# 2__FPGA.net
KiCad netlist of a schematic drawn in Altium Designer
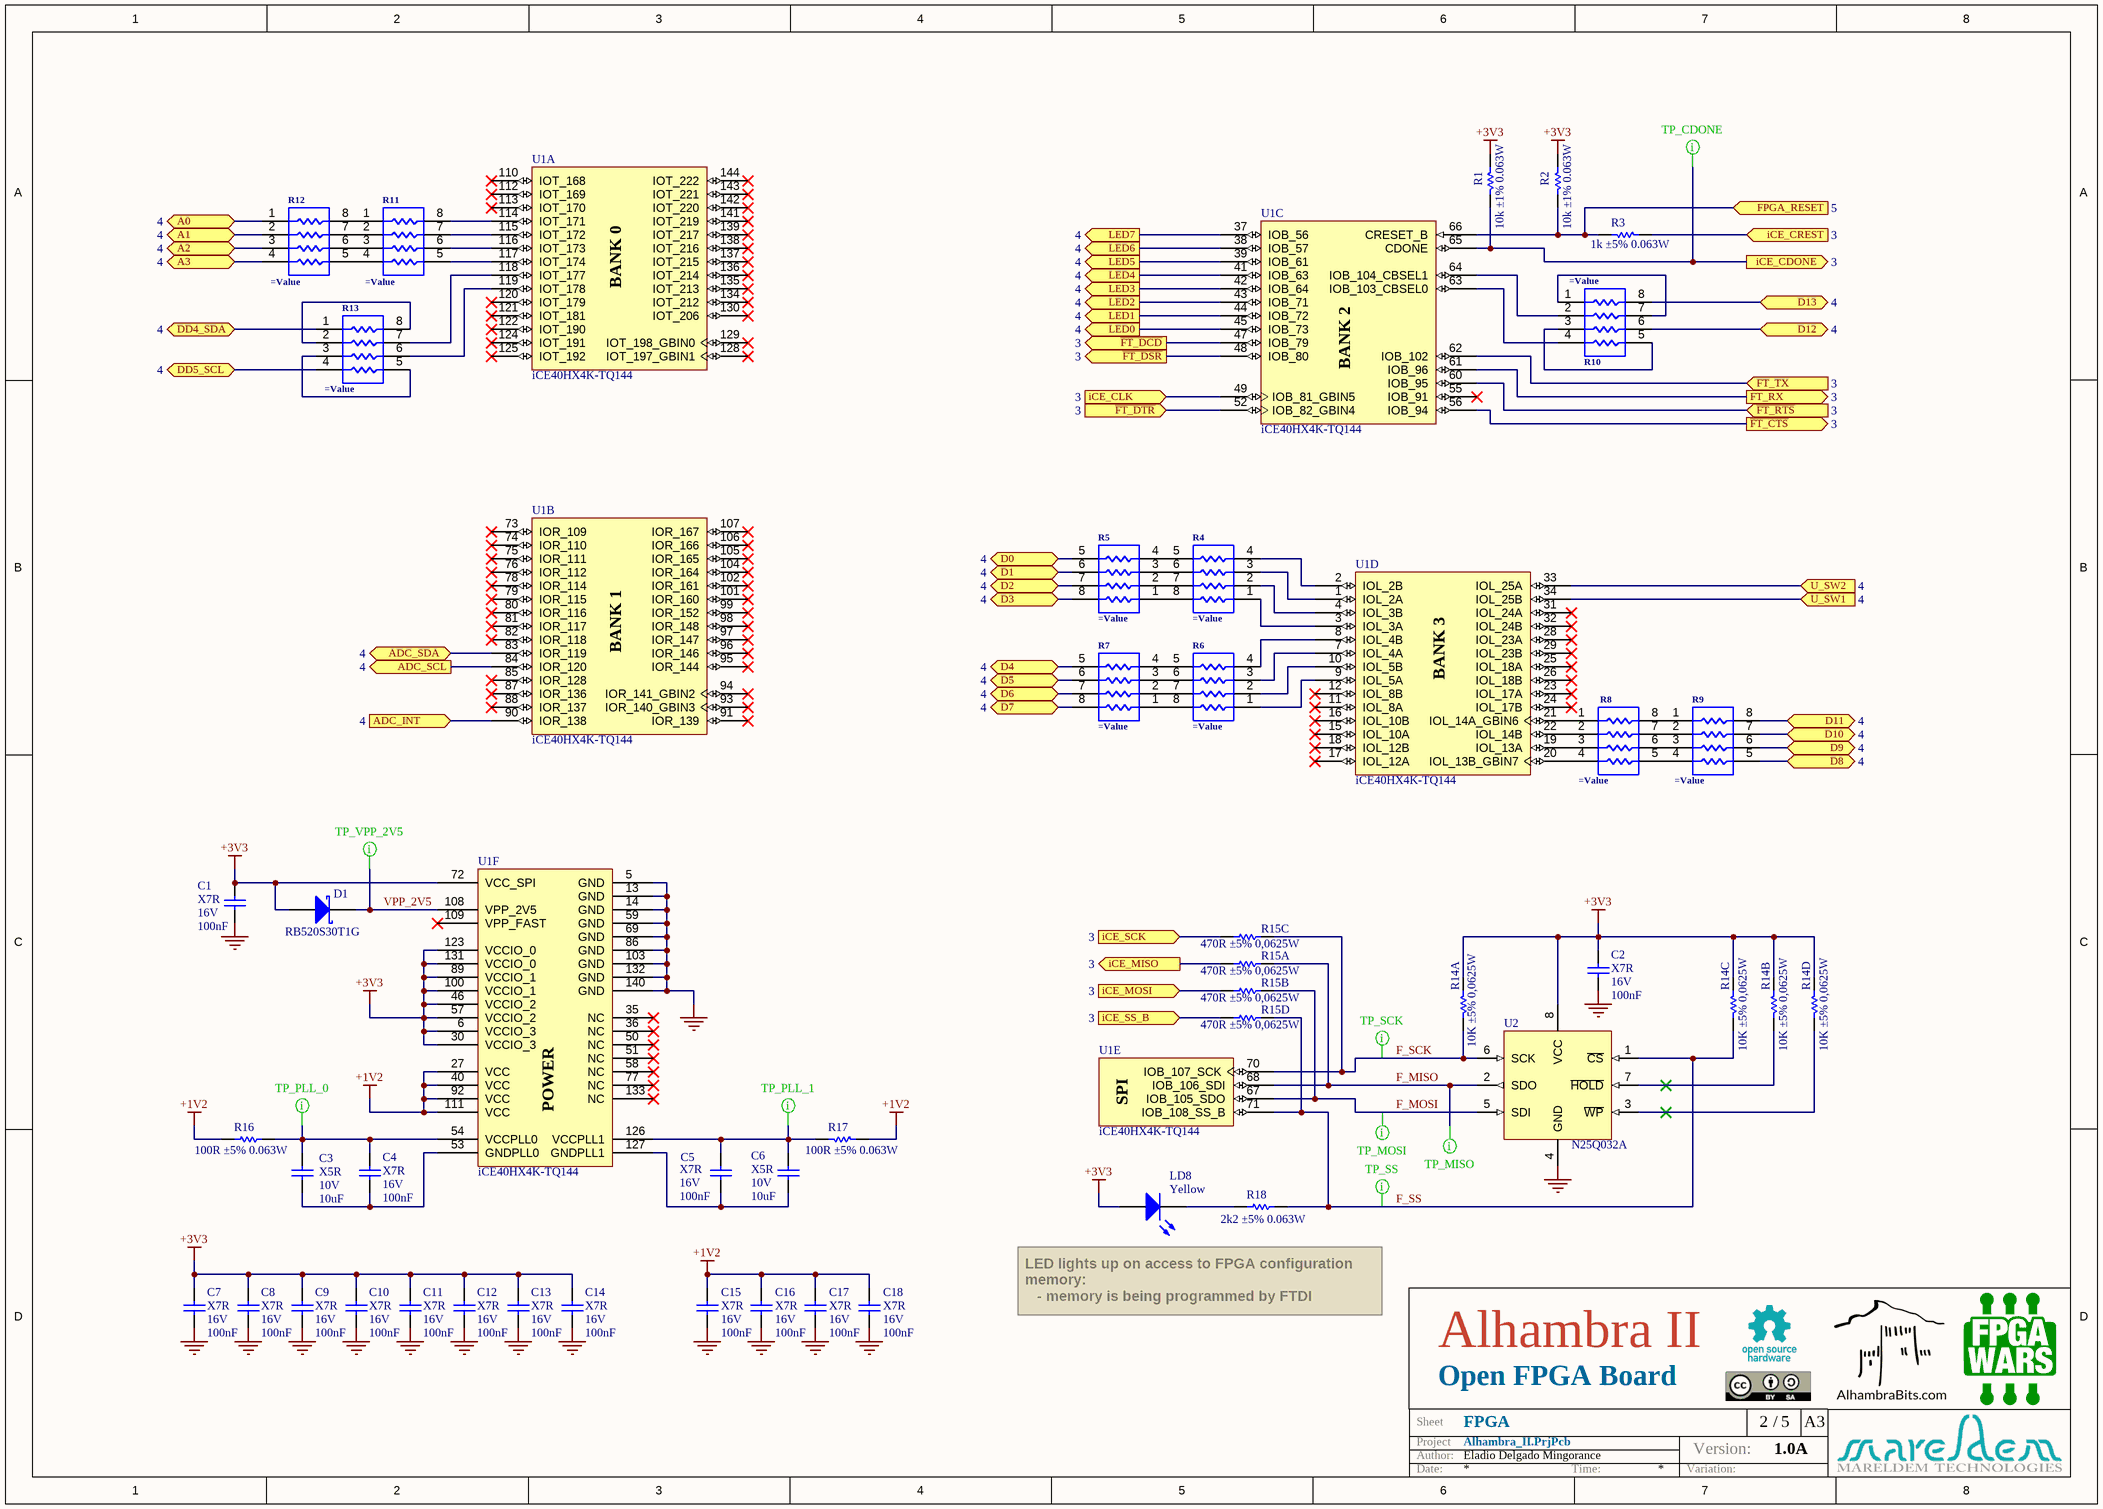
[diagram p0: [2]_FPGA.SchDoc]

(export (version "E")
  (design (tool "Eeschema 10.0.6"))
  (components
    (comp (ref "C1")
      (value "Capacitor")
      (footprint "C0402")
      (description "Capacitor SMD")
      (fields
        (field (name "DIELECTRIC") "X7R")
        (field (name "VOLTAGE") "16V")
        (field (name "CAPACITANCE") "100nF")
        (field (name "PART NUMBER") "C0402_100nF_16V_±10%")
        (field (name "TOLERANCE") "±10%")
      )
      (libsource (lib "Pasives_Capacitor_SMD") (part "Capacitor"))
    )
    (comp (ref "C2")
      (value "Capacitor")
      (footprint "C0402")
      (description "Capacitor SMD")
      (fields
        (field (name "DIELECTRIC") "X7R")
        (field (name "VOLTAGE") "16V")
        (field (name "CAPACITANCE") "100nF")
        (field (name "PART NUMBER") "C0402_100nF_16V_±10%")
        (field (name "TOLERANCE") "±10%")
      )
      (libsource (lib "Pasives_Capacitor_SMD") (part "Capacitor"))
    )
    (comp (ref "C3")
      (value "Capacitor")
      (footprint "C0603")
      (description "Capacitor SMD")
      (fields
        (field (name "DIELECTRIC") "X5R")
        (field (name "VOLTAGE") "10V")
        (field (name "CAPACITANCE") "10uF")
        (field (name "PART NUMBER") "C0603_10uF_10V_±10%")
        (field (name "TOLERANCE") "±10%")
      )
      (libsource (lib "") (part "Capacitor_1"))
    )
    (comp (ref "C4")
      (value "Capacitor")
      (footprint "C0402")
      (description "Capacitor SMD")
      (fields
        (field (name "DIELECTRIC") "X7R")
        (field (name "VOLTAGE") "16V")
        (field (name "CAPACITANCE") "100nF")
        (field (name "PART NUMBER") "C0402_100nF_16V_±10%")
        (field (name "TOLERANCE") "±10%")
      )
      (libsource (lib "Pasives_Capacitor_SMD") (part "Capacitor"))
    )
    (comp (ref "C5")
      (value "Capacitor")
      (footprint "C0402")
      (description "Capacitor SMD")
      (fields
        (field (name "DIELECTRIC") "X7R")
        (field (name "VOLTAGE") "16V")
        (field (name "CAPACITANCE") "100nF")
        (field (name "PART NUMBER") "C0402_100nF_16V_±10%")
        (field (name "TOLERANCE") "±10%")
      )
      (libsource (lib "Pasives_Capacitor_SMD") (part "Capacitor"))
    )
    (comp (ref "C6")
      (value "Capacitor")
      (footprint "C0603")
      (description "Capacitor SMD")
      (fields
        (field (name "DIELECTRIC") "X5R")
        (field (name "VOLTAGE") "10V")
        (field (name "CAPACITANCE") "10uF")
        (field (name "PART NUMBER") "C0603_10uF_10V_±10%")
        (field (name "TOLERANCE") "±10%")
      )
      (libsource (lib "") (part "Capacitor_1"))
    )
    (comp (ref "C7")
      (value "Capacitor")
      (footprint "C0402:C0402")
      (description "Capacitor SMD")
      (fields
        (field (name "DIELECTRIC") "X7R")
        (field (name "VOLTAGE") "16V")
        (field (name "CAPACITANCE") "100nF")
        (field (name "PART NUMBER") "C0402_100nF_16V_±10%")
        (field (name "TOLERANCE") "±10%")
      )
      (libsource (lib "Pasives_Capacitor_SMD") (part "Capacitor"))
    )
    (comp (ref "C8")
      (value "Capacitor")
      (footprint "C0402:C0402")
      (description "Capacitor SMD")
      (fields
        (field (name "DIELECTRIC") "X7R")
        (field (name "VOLTAGE") "16V")
        (field (name "CAPACITANCE") "100nF")
        (field (name "PART NUMBER") "C0402_100nF_16V_±10%")
        (field (name "TOLERANCE") "±10%")
      )
      (libsource (lib "Pasives_Capacitor_SMD") (part "Capacitor"))
    )
    (comp (ref "C9")
      (value "Capacitor")
      (footprint "C0402")
      (description "Capacitor SMD")
      (fields
        (field (name "DIELECTRIC") "X7R")
        (field (name "VOLTAGE") "16V")
        (field (name "CAPACITANCE") "100nF")
        (field (name "PART NUMBER") "C0402_100nF_16V_±10%")
        (field (name "TOLERANCE") "±10%")
      )
      (libsource (lib "Pasives_Capacitor_SMD") (part "Capacitor"))
    )
    (comp (ref "C10")
      (value "Capacitor")
      (footprint "C0402")
      (description "Capacitor SMD")
      (fields
        (field (name "DIELECTRIC") "X7R")
        (field (name "VOLTAGE") "16V")
        (field (name "CAPACITANCE") "100nF")
        (field (name "PART NUMBER") "C0402_100nF_16V_±10%")
        (field (name "TOLERANCE") "±10%")
      )
      (libsource (lib "Pasives_Capacitor_SMD") (part "Capacitor"))
    )
    (comp (ref "C11")
      (value "Capacitor")
      (footprint "C0402")
      (description "Capacitor SMD")
      (fields
        (field (name "DIELECTRIC") "X7R")
        (field (name "VOLTAGE") "16V")
        (field (name "CAPACITANCE") "100nF")
        (field (name "PART NUMBER") "C0402_100nF_16V_±10%")
        (field (name "TOLERANCE") "±10%")
      )
      (libsource (lib "Pasives_Capacitor_SMD") (part "Capacitor"))
    )
    (comp (ref "C12")
      (value "Capacitor")
      (footprint "C0402")
      (description "Capacitor SMD")
      (fields
        (field (name "DIELECTRIC") "X7R")
        (field (name "VOLTAGE") "16V")
        (field (name "CAPACITANCE") "100nF")
        (field (name "PART NUMBER") "C0402_100nF_16V_±10%")
        (field (name "TOLERANCE") "±10%")
      )
      (libsource (lib "Pasives_Capacitor_SMD") (part "Capacitor"))
    )
    (comp (ref "C13")
      (value "Capacitor")
      (footprint "C0402")
      (description "Capacitor SMD")
      (fields
        (field (name "DIELECTRIC") "X7R")
        (field (name "VOLTAGE") "16V")
        (field (name "CAPACITANCE") "100nF")
        (field (name "PART NUMBER") "C0402_100nF_16V_±10%")
        (field (name "TOLERANCE") "±10%")
      )
      (libsource (lib "Pasives_Capacitor_SMD") (part "Capacitor"))
    )
    (comp (ref "C14")
      (value "Capacitor")
      (footprint "C0402")
      (description "Capacitor SMD")
      (fields
        (field (name "DIELECTRIC") "X7R")
        (field (name "VOLTAGE") "16V")
        (field (name "CAPACITANCE") "100nF")
        (field (name "PART NUMBER") "C0402_100nF_16V_±10%")
        (field (name "TOLERANCE") "±10%")
      )
      (libsource (lib "Pasives_Capacitor_SMD") (part "Capacitor"))
    )
    (comp (ref "C15")
      (value "Capacitor")
      (footprint "C0402")
      (description "Capacitor SMD")
      (fields
        (field (name "DIELECTRIC") "X7R")
        (field (name "VOLTAGE") "16V")
        (field (name "CAPACITANCE") "100nF")
        (field (name "PART NUMBER") "C0402_100nF_16V_±10%")
        (field (name "TOLERANCE") "±10%")
      )
      (libsource (lib "Pasives_Capacitor_SMD") (part "Capacitor"))
    )
    (comp (ref "C16")
      (value "Capacitor")
      (footprint "C0402")
      (description "Capacitor SMD")
      (fields
        (field (name "DIELECTRIC") "X7R")
        (field (name "VOLTAGE") "16V")
        (field (name "CAPACITANCE") "100nF")
        (field (name "PART NUMBER") "C0402_100nF_16V_±10%")
        (field (name "TOLERANCE") "±10%")
      )
      (libsource (lib "Pasives_Capacitor_SMD") (part "Capacitor"))
    )
    (comp (ref "C17")
      (value "Capacitor")
      (footprint "C0402")
      (description "Capacitor SMD")
      (fields
        (field (name "DIELECTRIC") "X7R")
        (field (name "VOLTAGE") "16V")
        (field (name "CAPACITANCE") "100nF")
        (field (name "PART NUMBER") "C0402_100nF_16V_±10%")
        (field (name "TOLERANCE") "±10%")
      )
      (libsource (lib "Pasives_Capacitor_SMD") (part "Capacitor"))
    )
    (comp (ref "C18")
      (value "Capacitor")
      (footprint "C0402")
      (description "Capacitor SMD")
      (fields
        (field (name "DIELECTRIC") "X7R")
        (field (name "VOLTAGE") "16V")
        (field (name "CAPACITANCE") "100nF")
        (field (name "PART NUMBER") "C0402_100nF_16V_±10%")
        (field (name "TOLERANCE") "±10%")
      )
      (libsource (lib "Pasives_Capacitor_SMD") (part "Capacitor"))
    )
    (comp (ref "D1")
      (value "RB520S30T1G")
      (footprint "SOD523")
      (description "Schottky Diode")
      (fields (field (name "MANUFACTURER") "On Semiconductor"))
      (libsource (lib "Diodes") (part "Schottky"))
    )
    (comp (ref "LD8")
      (value "Yellow")
      (footprint "LED0603")
      (description "LED")
      (fields (field (name "PART NUMBER") "LED Yellow 0603 Wurth") (field (name "MANUFACTURER") "WE"))
      (libsource (lib "Optoelectronics") (part "LED"))
    )
    (comp (ref "R1")
      (value "10k ±1% 0.063W")
      (footprint "R0402")
      (description "Resistor, SMD")
      (fields (field (name "TOLERANCE") "±1%") (field (name "POWER") "0.063W"))
      (libsource (lib "Pasives_Resistor_SMD") (part "Resistor"))
    )
    (comp (ref "R2")
      (value "10k ±1% 0.063W")
      (footprint "R0402")
      (description "Resistor, SMD")
      (fields (field (name "TOLERANCE") "±1%") (field (name "POWER") "0.063W"))
      (libsource (lib "Pasives_Resistor_SMD") (part "Resistor"))
    )
    (comp (ref "R3")
      (value "1k ±5% 0.063W")
      (footprint "R0402")
      (description "Resistor, SMD")
      (fields (field (name "TOLERANCE") "±5%") (field (name "POWER") "0.063W"))
      (libsource (lib "Pasives_Resistor_SMD") (part "Resistor"))
    )
    (comp (ref "R4")
      (value "~")
      (footprint "4xArray_1206_Convex")
      (description "Resistor, Array 4x1")
      (fields
        (field (name "PART NUMBER") "4xArray_1206_Convex_100R_0,0625W_0,05")
        (field (name "POWER") "0,0625W")
      )
      (libsource (lib "Pasives_Resistor_SMD") (part "Resistor_4x"))
    )
    (comp (ref "R5")
      (value "~")
      (footprint "4xArray_1206_Convex")
      (description "Resistor, Array 4x1")
      (fields
        (field (name "PART NUMBER") "4xArray_1206_Convex_100R_0,0625W_0,05")
        (field (name "POWER") "0,0625W")
      )
      (libsource (lib "Pasives_Resistor_SMD") (part "Resistor_4x"))
    )
    (comp (ref "R6")
      (value "~")
      (footprint "4xArray_1206_Convex")
      (description "Resistor, Array 4x1")
      (fields
        (field (name "PART NUMBER") "4xArray_1206_Convex_100R_0,0625W_0,05")
        (field (name "POWER") "0,0625W")
      )
      (libsource (lib "Pasives_Resistor_SMD") (part "Resistor_4x"))
    )
    (comp (ref "R7")
      (value "~")
      (footprint "4xArray_1206_Convex")
      (description "Resistor, Array 4x1")
      (fields
        (field (name "PART NUMBER") "4xArray_1206_Convex_100R_0,0625W_0,05")
        (field (name "POWER") "0,0625W")
      )
      (libsource (lib "Pasives_Resistor_SMD") (part "Resistor_4x"))
    )
    (comp (ref "R8")
      (value "~")
      (footprint "4xArray_1206_Convex")
      (description "Resistor, Array 4x1")
      (fields
        (field (name "PART NUMBER") "4xArray_1206_Convex_100R_0,0625W_0,05")
        (field (name "POWER") "0,0625W")
      )
      (libsource (lib "Pasives_Resistor_SMD") (part "Resistor_4x"))
    )
    (comp (ref "R9")
      (value "~")
      (footprint "4xArray_1206_Convex")
      (description "Resistor, Array 4x1")
      (fields
        (field (name "PART NUMBER") "4xArray_1206_Convex_100R_0,0625W_0,05")
        (field (name "POWER") "0,0625W")
      )
      (libsource (lib "Pasives_Resistor_SMD") (part "Resistor_4x"))
    )
    (comp (ref "R10")
      (value "~")
      (footprint "4xArray_1206_Convex")
      (description "Resistor, Array 4x1")
      (fields
        (field (name "PART NUMBER") "4xArray_1206_Convex_100R_0,0625W_0,05")
        (field (name "POWER") "0,0625W")
      )
      (libsource (lib "Pasives_Resistor_SMD") (part "Resistor_4x"))
    )
    (comp (ref "R11")
      (value "~")
      (footprint "4xArray_1206_Convex")
      (description "Resistor, Array 4x1")
      (fields
        (field (name "PART NUMBER") "4xArray_1206_Convex_100R_0,0625W_0,05")
        (field (name "POWER") "0,0625W")
      )
      (libsource (lib "Pasives_Resistor_SMD") (part "Resistor_4x"))
    )
    (comp (ref "R12")
      (value "~")
      (footprint "4xArray_1206_Convex")
      (description "Resistor, Array 4x1")
      (fields
        (field (name "PART NUMBER") "4xArray_1206_Convex_100R_0,0625W_0,05")
        (field (name "POWER") "0,0625W")
      )
      (libsource (lib "Pasives_Resistor_SMD") (part "Resistor_4x"))
    )
    (comp (ref "R13")
      (value "~")
      (footprint "4xArray_1206_Convex")
      (description "Resistor, Array 4x1")
      (fields
        (field (name "PART NUMBER") "4xArray_1206_Convex_100R_0,0625W_0,05")
        (field (name "POWER") "0,0625W")
      )
      (libsource (lib "Pasives_Resistor_SMD") (part "Resistor_4x"))
    )
    (comp (ref "R14")
      (value "10K ±5% 0,0625W")
      (footprint "4xArray_1206_Convex")
      (description "Resistor")
      (fields (field (name "TOLERANCE") "±5%") (field (name "POWER") "0,0625W"))
      (libsource (lib "Pasives_Resistor_SMD") (part "Resistor_x4_Parts"))
    )
    (comp (ref "R15")
      (value "470R ±5% 0,0625W")
      (footprint "4xArray_1206_Convex")
      (description "Resistor")
      (fields (field (name "TOLERANCE") "±5%") (field (name "POWER") "0,0625W"))
      (libsource (lib "Pasives_Resistor_SMD") (part "Resistor_x4_Parts"))
    )
    (comp (ref "R16")
      (value "100R ±5% 0.063W")
      (footprint "R0402")
      (description "Resistor, SMD")
      (fields (field (name "TOLERANCE") "±5%") (field (name "POWER") "0.063W"))
      (libsource (lib "Pasives_Resistor_SMD") (part "Resistor"))
    )
    (comp (ref "R17")
      (value "100R ±5% 0.063W")
      (footprint "R0402")
      (description "Resistor, SMD")
      (fields (field (name "TOLERANCE") "±5%") (field (name "POWER") "0.063W"))
      (libsource (lib "Pasives_Resistor_SMD") (part "Resistor"))
    )
    (comp (ref "R18")
      (value "2k2 ±5% 0.063W")
      (footprint "R0402")
      (description "Resistor, SMD")
      (fields (field (name "TOLERANCE") "±5%") (field (name "POWER") "0.063W"))
      (libsource (lib "Pasives_Resistor_SMD") (part "Resistor"))
    )
    (comp (ref "U1")
      (value "iCE40HX4K-TQ144")
      (footprint "TQFP-144_HX4K_FPGAwars")
      (fields (field (name "PART NUMBER") "iCE40-HX4K") (field (name "MANUFACTURER") "Lattice"))
      (libsource (lib "FPGA") (part "iCE40HX4K-TQ144"))
    )
    (comp (ref "U2")
      (value "N25Q032A")
      (footprint "DFN-8 6x5mm")
      (description "NOR Flash Memory, serial")
      (fields (field (name "MANUFACTURER") "Micron"))
      (libsource (lib "Memory_Serial") (part "N25Q032A"))
    )
  )
  (nets
    (net (code "1") (name "+1V2") (class "Default")
      (node (ref "C15") (pin "2") (pinfunction "2_2") (pintype "passive"))
      (node (ref "C16") (pin "2") (pinfunction "2_2") (pintype "passive"))
      (node (ref "C17") (pin "2") (pinfunction "2_2") (pintype "passive"))
      (node (ref "C18") (pin "2") (pinfunction "2_2") (pintype "passive"))
      (node (ref "R16") (pin "2") (pinfunction "2_2") (pintype "passive"))
      (node (ref "R17") (pin "2") (pinfunction "2_2") (pintype "passive"))
      (node (ref "U1") (pin "111") (pinfunction "VCC_111") (pintype "power_in"))
      (node (ref "U1") (pin "27") (pinfunction "VCC_27") (pintype "power_in"))
      (node (ref "U1") (pin "40") (pinfunction "VCC_40") (pintype "power_in"))
      (node (ref "U1") (pin "92") (pinfunction "VCC_92") (pintype "power_in"))
    )
    (net (code "2") (name "+3V3") (class "Default")
      (node (ref "C1") (pin "2") (pinfunction "2_2") (pintype "passive"))
      (node (ref "C10") (pin "2") (pinfunction "2_2") (pintype "passive"))
      (node (ref "C11") (pin "2") (pinfunction "2_2") (pintype "passive"))
      (node (ref "C12") (pin "2") (pinfunction "2_2") (pintype "passive"))
      (node (ref "C13") (pin "2") (pinfunction "2_2") (pintype "passive"))
      (node (ref "C14") (pin "2") (pinfunction "2_2") (pintype "passive"))
      (node (ref "C2") (pin "1") (pinfunction "1_1") (pintype "passive"))
      (node (ref "C7") (pin "2") (pinfunction "2_2") (pintype "passive"))
      (node (ref "C8") (pin "2") (pinfunction "2_2") (pintype "passive"))
      (node (ref "C9") (pin "2") (pinfunction "2_2") (pintype "passive"))
      (node (ref "D1") (pin "A") (pinfunction "A_A") (pintype "passive"))
      (node (ref "LD8") (pin "A") (pinfunction "A_A") (pintype "passive"))
      (node (ref "R1") (pin "1") (pinfunction "1_1") (pintype "passive"))
      (node (ref "R14") (pin "1") (pinfunction "1_1") (pintype "passive"))
      (node (ref "R14") (pin "2") (pinfunction "2_2") (pintype "passive"))
      (node (ref "R14") (pin "3") (pinfunction "3_3") (pintype "passive"))
      (node (ref "R14") (pin "4") (pinfunction "4_4") (pintype "passive"))
      (node (ref "R2") (pin "1") (pinfunction "1_1") (pintype "passive"))
      (node (ref "U1") (pin "100") (pinfunction "VCCIO_1_100") (pintype "power_in"))
      (node (ref "U1") (pin "123") (pinfunction "VCCIO_0_123") (pintype "power_in"))
      (node (ref "U1") (pin "131") (pinfunction "VCCIO_0_131") (pintype "power_in"))
      (node (ref "U1") (pin "30") (pinfunction "VCCIO_3_30") (pintype "power_in"))
      (node (ref "U1") (pin "46") (pinfunction "VCCIO_2_46") (pintype "power_in"))
      (node (ref "U1") (pin "57") (pinfunction "VCCIO_2_57") (pintype "power_in"))
      (node (ref "U1") (pin "6") (pinfunction "VCCIO_3_6") (pintype "power_in"))
      (node (ref "U1") (pin "72") (pinfunction "VCC_SPI_72") (pintype "power_in"))
      (node (ref "U1") (pin "89") (pinfunction "VCCIO_1_89") (pintype "power_in"))
      (node (ref "U2") (pin "8") (pinfunction "VCC_8") (pintype "power_in"))
    )
    (net (code "3") (name "/A0") (class "Default")
      (node (ref "R12") (pin "1") (pinfunction "1_1") (pintype "passive"))
    )
    (net (code "4") (name "/A1") (class "Default")
      (node (ref "R12") (pin "2") (pinfunction "2_2") (pintype "passive"))
    )
    (net (code "5") (name "/A2") (class "Default")
      (node (ref "R12") (pin "3") (pinfunction "3_3") (pintype "passive"))
    )
    (net (code "6") (name "/A3") (class "Default")
      (node (ref "R12") (pin "4") (pinfunction "4_4") (pintype "passive"))
    )
    (net (code "7") (name "/ADC_INT") (class "Default")
      (node (ref "U1") (pin "90") (pinfunction "IOR_138_90") (pintype "bidirectional"))
    )
    (net (code "8") (name "/ADC_SCL") (class "Default")
      (node (ref "U1") (pin "84") (pinfunction "IOR_120_84") (pintype "bidirectional"))
    )
    (net (code "9") (name "/ADC_SDA") (class "Default")
      (node (ref "U1") (pin "83") (pinfunction "IOR_119_83") (pintype "bidirectional"))
    )
    (net (code "10") (name "/D0") (class "Default")
      (node (ref "R5") (pin "5") (pinfunction "5_5") (pintype "passive"))
    )
    (net (code "11") (name "/D1") (class "Default")
      (node (ref "R5") (pin "6") (pinfunction "6_6") (pintype "passive"))
    )
    (net (code "12") (name "/D2") (class "Default")
      (node (ref "R5") (pin "7") (pinfunction "7_7") (pintype "passive"))
    )
    (net (code "13") (name "/D3") (class "Default")
      (node (ref "R5") (pin "8") (pinfunction "8_8") (pintype "passive"))
    )
    (net (code "14") (name "/D4") (class "Default")
      (node (ref "R7") (pin "5") (pinfunction "5_5") (pintype "passive"))
    )
    (net (code "15") (name "/D5") (class "Default")
      (node (ref "R7") (pin "6") (pinfunction "6_6") (pintype "passive"))
    )
    (net (code "16") (name "/D6") (class "Default")
      (node (ref "R7") (pin "7") (pinfunction "7_7") (pintype "passive"))
    )
    (net (code "17") (name "/D7") (class "Default")
      (node (ref "R7") (pin "8") (pinfunction "8_8") (pintype "passive"))
    )
    (net (code "18") (name "/D8") (class "Default")
      (node (ref "R9") (pin "5") (pinfunction "5_5") (pintype "passive"))
    )
    (net (code "19") (name "/D9") (class "Default")
      (node (ref "R9") (pin "6") (pinfunction "6_6") (pintype "passive"))
    )
    (net (code "20") (name "/D10") (class "Default")
      (node (ref "R9") (pin "7") (pinfunction "7_7") (pintype "passive"))
    )
    (net (code "21") (name "/D11") (class "Default")
      (node (ref "R9") (pin "8") (pinfunction "8_8") (pintype "passive"))
    )
    (net (code "22") (name "/D12") (class "Default")
      (node (ref "R10") (pin "6") (pinfunction "6_6") (pintype "passive"))
    )
    (net (code "23") (name "/D13") (class "Default")
      (node (ref "R10") (pin "8") (pinfunction "8_8") (pintype "passive"))
    )
    (net (code "24") (name "/DD4_SDA") (class "Default")
      (node (ref "R13") (pin "1") (pinfunction "1_1") (pintype "passive"))
    )
    (net (code "25") (name "/DD5_SCL") (class "Default")
      (node (ref "R13") (pin "4") (pinfunction "4_4") (pintype "passive"))
    )
    (net (code "26") (name "/FPGA_RESET") (class "Default")
      (node (ref "R2") (pin "2") (pinfunction "2_2") (pintype "passive"))
      (node (ref "R3") (pin "2") (pinfunction "2_2") (pintype "passive"))
      (node (ref "U1") (pin "66") (pinfunction "CRESET_B_66") (pintype "input"))
    )
    (net (code "27") (name "/FT_CTS") (class "Default")
      (node (ref "U1") (pin "56") (pinfunction "IOB_94_56") (pintype "bidirectional"))
    )
    (net (code "28") (name "/FT_DCD") (class "Default")
      (node (ref "U1") (pin "47") (pinfunction "IOB_79_47") (pintype "bidirectional"))
    )
    (net (code "29") (name "/FT_DSR") (class "Default")
      (node (ref "U1") (pin "48") (pinfunction "IOB_80_48") (pintype "bidirectional"))
    )
    (net (code "30") (name "/FT_DTR") (class "Default")
      (node (ref "U1") (pin "52") (pinfunction "IOB_82_GBIN4_52") (pintype "bidirectional"))
    )
    (net (code "31") (name "/FT_RTS") (class "Default")
      (node (ref "U1") (pin "60") (pinfunction "IOB_95_60") (pintype "bidirectional"))
    )
    (net (code "32") (name "/FT_RX") (class "Default")
      (node (ref "U1") (pin "61") (pinfunction "IOB_96_61") (pintype "bidirectional"))
    )
    (net (code "33") (name "/FT_TX") (class "Default")
      (node (ref "U1") (pin "62") (pinfunction "IOB_102_62") (pintype "bidirectional"))
    )
    (net (code "34") (name "/F_MISO") (class "Default")
      (node (ref "R15") (pin "8") (pinfunction "8_8") (pintype "passive"))
      (node (ref "U1") (pin "68") (pinfunction "IOB_45_SDI_68") (pintype "bidirectional"))
      (node (ref "U2") (pin "2") (pinfunction "SDO_2") (pintype "output"))
    )
    (net (code "35") (name "/F_MOSI") (class "Default")
      (node (ref "R15") (pin "7") (pinfunction "7_7") (pintype "passive"))
      (node (ref "U1") (pin "67") (pinfunction "IOB_44_SDO_67") (pintype "bidirectional"))
      (node (ref "U2") (pin "5") (pinfunction "SDI_5") (pintype "input"))
    )
    (net (code "36") (name "/F_SCK") (class "Default")
      (node (ref "R14") (pin "8") (pinfunction "8_8") (pintype "passive"))
      (node (ref "R15") (pin "6") (pinfunction "6_6") (pintype "passive"))
      (node (ref "U1") (pin "70") (pinfunction "IOB_46_SCK_70") (pintype "bidirectional"))
      (node (ref "U2") (pin "6") (pinfunction "SCK_6") (pintype "input"))
    )
    (net (code "37") (name "/F_SS") (class "Default")
      (node (ref "R14") (pin "6") (pinfunction "6_6") (pintype "passive"))
      (node (ref "R15") (pin "5") (pinfunction "5_5") (pintype "passive"))
      (node (ref "R18") (pin "2") (pinfunction "2_2") (pintype "passive"))
      (node (ref "U1") (pin "71") (pinfunction "IOB_47_SS_B_71") (pintype "bidirectional"))
      (node (ref "U2") (pin "1") (pinfunction "CS_1") (pintype "input"))
    )
    (net (code "38") (name "/LED0") (class "Default")
      (node (ref "U1") (pin "45") (pinfunction "IOB_73_45") (pintype "bidirectional"))
    )
    (net (code "39") (name "/LED1") (class "Default")
      (node (ref "U1") (pin "44") (pinfunction "IOB_72_44") (pintype "bidirectional"))
    )
    (net (code "40") (name "/LED2") (class "Default")
      (node (ref "U1") (pin "43") (pinfunction "IOB_71_43") (pintype "bidirectional"))
    )
    (net (code "41") (name "/LED3") (class "Default")
      (node (ref "U1") (pin "42") (pinfunction "IOB_64_42") (pintype "bidirectional"))
    )
    (net (code "42") (name "/LED4") (class "Default")
      (node (ref "U1") (pin "41") (pinfunction "IOB_63_41") (pintype "bidirectional"))
    )
    (net (code "43") (name "/LED5") (class "Default")
      (node (ref "U1") (pin "39") (pinfunction "IOB_61_39") (pintype "bidirectional"))
    )
    (net (code "44") (name "/LED6") (class "Default")
      (node (ref "U1") (pin "38") (pinfunction "IOB_57_38") (pintype "bidirectional"))
    )
    (net (code "45") (name "/LED7") (class "Default")
      (node (ref "U1") (pin "37") (pinfunction "IOB_56_37") (pintype "bidirectional"))
    )
    (net (code "46") (name "/U_SW1") (class "Default")
      (node (ref "U1") (pin "34") (pinfunction "IOL_25B_34") (pintype "bidirectional"))
    )
    (net (code "47") (name "/U_SW2") (class "Default")
      (node (ref "U1") (pin "33") (pinfunction "IOL_25A_33") (pintype "bidirectional"))
    )
    (net (code "48") (name "/VPP_2V5") (class "Default")
      (node (ref "D1") (pin "k") (pinfunction "K_k") (pintype "passive"))
      (node (ref "U1") (pin "108") (pinfunction "VPP_2V5_108") (pintype "power_in"))
    )
    (net (code "49") (name "/iCE_CDONE") (class "Default")
      (node (ref "R1") (pin "2") (pinfunction "2_2") (pintype "passive"))
      (node (ref "U1") (pin "65") (pinfunction "CDONE_65") (pintype "bidirectional"))
    )
    (net (code "50") (name "/iCE_CLK") (class "Default")
      (node (ref "U1") (pin "49") (pinfunction "IOB_81_GBIN5_49") (pintype "bidirectional"))
    )
    (net (code "51") (name "/iCE_CREST") (class "Default")
      (node (ref "R3") (pin "1") (pinfunction "1_1") (pintype "passive"))
    )
    (net (code "52") (name "/iCE_MISO") (class "Default")
      (node (ref "R15") (pin "1") (pinfunction "1_1") (pintype "passive"))
    )
    (net (code "53") (name "/iCE_MOSI") (class "Default")
      (node (ref "R15") (pin "2") (pinfunction "2_2") (pintype "passive"))
    )
    (net (code "54") (name "/iCE_SCK") (class "Default")
      (node (ref "R15") (pin "3") (pinfunction "3_3") (pintype "passive"))
    )
    (net (code "55") (name "/iCE_SS_B") (class "Default")
      (node (ref "R15") (pin "4") (pinfunction "4_4") (pintype "passive"))
    )
    (net (code "56") (name "GND") (class "Default")
      (node (ref "C1") (pin "1") (pinfunction "1_1") (pintype "passive"))
      (node (ref "C10") (pin "1") (pinfunction "1_1") (pintype "passive"))
      (node (ref "C11") (pin "1") (pinfunction "1_1") (pintype "passive"))
      (node (ref "C12") (pin "1") (pinfunction "1_1") (pintype "passive"))
      (node (ref "C13") (pin "1") (pinfunction "1_1") (pintype "passive"))
      (node (ref "C14") (pin "1") (pinfunction "1_1") (pintype "passive"))
      (node (ref "C15") (pin "1") (pinfunction "1_1") (pintype "passive"))
      (node (ref "C16") (pin "1") (pinfunction "1_1") (pintype "passive"))
      (node (ref "C17") (pin "1") (pinfunction "1_1") (pintype "passive"))
      (node (ref "C18") (pin "1") (pinfunction "1_1") (pintype "passive"))
      (node (ref "C2") (pin "2") (pinfunction "2_2") (pintype "passive"))
      (node (ref "C7") (pin "1") (pinfunction "1_1") (pintype "passive"))
      (node (ref "C8") (pin "1") (pinfunction "1_1") (pintype "passive"))
      (node (ref "C9") (pin "1") (pinfunction "1_1") (pintype "passive"))
      (node (ref "U1") (pin "103") (pinfunction "GND_103") (pintype "power_in"))
      (node (ref "U1") (pin "13") (pinfunction "GND_13") (pintype "power_in"))
      (node (ref "U1") (pin "132") (pinfunction "GND_132") (pintype "power_in"))
      (node (ref "U1") (pin "14") (pinfunction "GND_14") (pintype "power_in"))
      (node (ref "U1") (pin "140") (pinfunction "GND_140") (pintype "power_in"))
      (node (ref "U1") (pin "5") (pinfunction "GND_5") (pintype "power_in"))
      (node (ref "U1") (pin "59") (pinfunction "GND_59") (pintype "power_in"))
      (node (ref "U1") (pin "69") (pinfunction "GND_69") (pintype "power_in"))
      (node (ref "U1") (pin "86") (pinfunction "GND_86") (pintype "power_in"))
      (node (ref "U2") (pin "4") (pinfunction "GND_4") (pintype "power_in"))
    )
    (net (code "57") (name "Net-(LD8-PadK)") (class "Default")
      (node (ref "LD8") (pin "K") (pinfunction "K_K") (pintype "passive"))
      (node (ref "R18") (pin "1") (pinfunction "1_1") (pintype "passive"))
    )
    (net (code "58") (name "Net-(R4-Pad5)") (class "Default")
      (node (ref "R4") (pin "5") (pinfunction "5_5") (pintype "passive"))
      (node (ref "R5") (pin "4") (pinfunction "4_4") (pintype "passive"))
    )
    (net (code "59") (name "Net-(R4-Pad6)") (class "Default")
      (node (ref "R4") (pin "6") (pinfunction "6_6") (pintype "passive"))
      (node (ref "R5") (pin "3") (pinfunction "3_3") (pintype "passive"))
    )
    (net (code "60") (name "Net-(R4-Pad7)") (class "Default")
      (node (ref "R4") (pin "7") (pinfunction "7_7") (pintype "passive"))
      (node (ref "R5") (pin "2") (pinfunction "2_2") (pintype "passive"))
    )
    (net (code "61") (name "Net-(R4-Pad8)") (class "Default")
      (node (ref "R4") (pin "8") (pinfunction "8_8") (pintype "passive"))
      (node (ref "R5") (pin "1") (pinfunction "1_1") (pintype "passive"))
    )
    (net (code "62") (name "Net-(R6-Pad5)") (class "Default")
      (node (ref "R6") (pin "5") (pinfunction "5_5") (pintype "passive"))
      (node (ref "R7") (pin "4") (pinfunction "4_4") (pintype "passive"))
    )
    (net (code "63") (name "Net-(R6-Pad6)") (class "Default")
      (node (ref "R6") (pin "6") (pinfunction "6_6") (pintype "passive"))
      (node (ref "R7") (pin "3") (pinfunction "3_3") (pintype "passive"))
    )
    (net (code "64") (name "Net-(R6-Pad7)") (class "Default")
      (node (ref "R6") (pin "7") (pinfunction "7_7") (pintype "passive"))
      (node (ref "R7") (pin "2") (pinfunction "2_2") (pintype "passive"))
    )
    (net (code "65") (name "Net-(R6-Pad8)") (class "Default")
      (node (ref "R6") (pin "8") (pinfunction "8_8") (pintype "passive"))
      (node (ref "R7") (pin "1") (pinfunction "1_1") (pintype "passive"))
    )
    (net (code "66") (name "Net-(R8-Pad5)") (class "Default")
      (node (ref "R8") (pin "5") (pinfunction "5_5") (pintype "passive"))
      (node (ref "R9") (pin "4") (pinfunction "4_4") (pintype "passive"))
    )
    (net (code "67") (name "Net-(R8-Pad6)") (class "Default")
      (node (ref "R8") (pin "6") (pinfunction "6_6") (pintype "passive"))
      (node (ref "R9") (pin "3") (pinfunction "3_3") (pintype "passive"))
    )
    (net (code "68") (name "Net-(R8-Pad7)") (class "Default")
      (node (ref "R8") (pin "7") (pinfunction "7_7") (pintype "passive"))
      (node (ref "R9") (pin "2") (pinfunction "2_2") (pintype "passive"))
    )
    (net (code "69") (name "Net-(R8-Pad8)") (class "Default")
      (node (ref "R8") (pin "8") (pinfunction "8_8") (pintype "passive"))
      (node (ref "R9") (pin "1") (pinfunction "1_1") (pintype "passive"))
    )
    (net (code "70") (name "Net-(R10-Pad1)") (class "Default")
      (node (ref "R10") (pin "1") (pinfunction "1_1") (pintype "passive"))
      (node (ref "R10") (pin "7") (pinfunction "7_7") (pintype "passive"))
    )
    (net (code "71") (name "Net-(R10-Pad3)") (class "Default")
      (node (ref "R10") (pin "3") (pinfunction "3_3") (pintype "passive"))
      (node (ref "R10") (pin "5") (pinfunction "5_5") (pintype "passive"))
    )
    (net (code "72") (name "Net-(R11-Pad1)") (class "Default")
      (node (ref "R11") (pin "1") (pinfunction "1_1") (pintype "passive"))
      (node (ref "R12") (pin "8") (pinfunction "8_8") (pintype "passive"))
    )
    (net (code "73") (name "Net-(R11-Pad2)") (class "Default")
      (node (ref "R11") (pin "2") (pinfunction "2_2") (pintype "passive"))
      (node (ref "R12") (pin "7") (pinfunction "7_7") (pintype "passive"))
    )
    (net (code "74") (name "Net-(R11-Pad3)") (class "Default")
      (node (ref "R11") (pin "3") (pinfunction "3_3") (pintype "passive"))
      (node (ref "R12") (pin "6") (pinfunction "6_6") (pintype "passive"))
    )
    (net (code "75") (name "Net-(R11-Pad4)") (class "Default")
      (node (ref "R11") (pin "4") (pinfunction "4_4") (pintype "passive"))
      (node (ref "R12") (pin "5") (pinfunction "5_5") (pintype "passive"))
    )
    (net (code "76") (name "Net-(R13-Pad2)") (class "Default")
      (node (ref "R13") (pin "2") (pinfunction "2_2") (pintype "passive"))
      (node (ref "R13") (pin "8") (pinfunction "8_8") (pintype "passive"))
    )
    (net (code "77") (name "Net-(R13-Pad3)") (class "Default")
      (node (ref "R13") (pin "3") (pinfunction "3_3") (pintype "passive"))
      (node (ref "R13") (pin "5") (pinfunction "5_5") (pintype "passive"))
    )
    (net (code "78") (name "Net-(U1A-IOT_171)") (class "Default")
      (node (ref "R11") (pin "8") (pinfunction "8_8") (pintype "passive"))
      (node (ref "U1") (pin "114") (pinfunction "IOT_171_114") (pintype "bidirectional"))
    )
    (net (code "79") (name "Net-(U1A-IOT_172)") (class "Default")
      (node (ref "R11") (pin "7") (pinfunction "7_7") (pintype "passive"))
      (node (ref "U1") (pin "115") (pinfunction "IOT_172_115") (pintype "bidirectional"))
    )
    (net (code "80") (name "Net-(U1A-IOT_173)") (class "Default")
      (node (ref "R11") (pin "6") (pinfunction "6_6") (pintype "passive"))
      (node (ref "U1") (pin "116") (pinfunction "IOT_173_116") (pintype "bidirectional"))
    )
    (net (code "81") (name "Net-(U1A-IOT_174)") (class "Default")
      (node (ref "R11") (pin "5") (pinfunction "5_5") (pintype "passive"))
      (node (ref "U1") (pin "117") (pinfunction "IOT_174_117") (pintype "bidirectional"))
    )
    (net (code "82") (name "Net-(U1A-IOT_177)") (class "Default")
      (node (ref "R13") (pin "7") (pinfunction "7_7") (pintype "passive"))
      (node (ref "U1") (pin "118") (pinfunction "IOT_177_118") (pintype "bidirectional"))
    )
    (net (code "83") (name "Net-(U1A-IOT_178)") (class "Default")
      (node (ref "R13") (pin "6") (pinfunction "6_6") (pintype "passive"))
      (node (ref "U1") (pin "119") (pinfunction "IOT_178_119") (pintype "bidirectional"))
    )
    (net (code "84") (name "Net-(U1C-IOB_103_CBSEL0)") (class "Default")
      (node (ref "R10") (pin "4") (pinfunction "4_4") (pintype "passive"))
      (node (ref "U1") (pin "63") (pinfunction "IOB_103_CBSEL0_63") (pintype "bidirectional"))
    )
    (net (code "85") (name "Net-(U1C-IOB_104_CBSEL1)") (class "Default")
      (node (ref "R10") (pin "2") (pinfunction "2_2") (pintype "passive"))
      (node (ref "U1") (pin "64") (pinfunction "IOB_104_CBSEL1_64") (pintype "bidirectional"))
    )
    (net (code "86") (name "Net-(U1D-IOL_2A)") (class "Default")
      (node (ref "R4") (pin "3") (pinfunction "3_3") (pintype "passive"))
      (node (ref "U1") (pin "1") (pinfunction "IOL_2A_1") (pintype "bidirectional"))
    )
    (net (code "87") (name "Net-(U1D-IOL_2B)") (class "Default")
      (node (ref "R4") (pin "4") (pinfunction "4_4") (pintype "passive"))
      (node (ref "U1") (pin "2") (pinfunction "IOL_2B_2") (pintype "bidirectional"))
    )
    (net (code "88") (name "Net-(U1D-IOL_3A)") (class "Default")
      (node (ref "R4") (pin "1") (pinfunction "1_1") (pintype "passive"))
      (node (ref "U1") (pin "3") (pinfunction "IOL_3A_3") (pintype "bidirectional"))
    )
    (net (code "89") (name "Net-(U1D-IOL_3B)") (class "Default")
      (node (ref "R4") (pin "2") (pinfunction "2_2") (pintype "passive"))
      (node (ref "U1") (pin "4") (pinfunction "IOL_3B_4") (pintype "bidirectional"))
    )
    (net (code "90") (name "Net-(U1D-IOL_4A)") (class "Default")
      (node (ref "R6") (pin "3") (pinfunction "3_3") (pintype "passive"))
      (node (ref "U1") (pin "7") (pinfunction "IOL_4A_7") (pintype "bidirectional"))
    )
    (net (code "91") (name "Net-(U1D-IOL_4B)") (class "Default")
      (node (ref "R6") (pin "4") (pinfunction "4_4") (pintype "passive"))
      (node (ref "U1") (pin "8") (pinfunction "IOL_4B_8") (pintype "bidirectional"))
    )
    (net (code "92") (name "Net-(U1D-IOL_5A)") (class "Default")
      (node (ref "R6") (pin "1") (pinfunction "1_1") (pintype "passive"))
      (node (ref "U1") (pin "9") (pinfunction "IOL_5A_9") (pintype "bidirectional"))
    )
    (net (code "93") (name "Net-(U1D-IOL_5B)") (class "Default")
      (node (ref "R6") (pin "2") (pinfunction "2_2") (pintype "passive"))
      (node (ref "U1") (pin "10") (pinfunction "IOL_5B_10") (pintype "bidirectional"))
    )
    (net (code "94") (name "Net-(U1D-IOL_13A)") (class "Default")
      (node (ref "R8") (pin "3") (pinfunction "3_3") (pintype "passive"))
      (node (ref "U1") (pin "19") (pinfunction "IOL_13A_19") (pintype "bidirectional"))
    )
    (net (code "95") (name "Net-(U1D-IOL_13B_GBIN7)") (class "Default")
      (node (ref "R8") (pin "4") (pinfunction "4_4") (pintype "passive"))
      (node (ref "U1") (pin "20") (pinfunction "IOL_13B_GBIN7_20") (pintype "bidirectional"))
    )
    (net (code "96") (name "Net-(U1D-IOL_14A_GBIN6)") (class "Default")
      (node (ref "R8") (pin "1") (pinfunction "1_1") (pintype "passive"))
      (node (ref "U1") (pin "21") (pinfunction "IOL_14A_GBIN6_21") (pintype "bidirectional"))
    )
    (net (code "97") (name "Net-(U1D-IOL_14B)") (class "Default")
      (node (ref "R8") (pin "2") (pinfunction "2_2") (pintype "passive"))
      (node (ref "U1") (pin "22") (pinfunction "IOL_14B_22") (pintype "bidirectional"))
    )
    (net (code "98") (name "Net-(U1F-GNDPLL0)") (class "Default")
      (node (ref "C3") (pin "2") (pinfunction "2_2") (pintype "passive"))
      (node (ref "C4") (pin "1") (pinfunction "1_1") (pintype "passive"))
      (node (ref "U1") (pin "53") (pinfunction "GNDPLL0_53") (pintype "power_in"))
    )
    (net (code "99") (name "Net-(U1F-GNDPLL1)") (class "Default")
      (node (ref "C5") (pin "1") (pinfunction "1_1") (pintype "passive"))
      (node (ref "C6") (pin "1") (pinfunction "1_1") (pintype "passive"))
      (node (ref "U1") (pin "127") (pinfunction "GNDPLL1_127") (pintype "power_in"))
    )
    (net (code "100") (name "Net-(U1F-VCCPLL0)") (class "Default")
      (node (ref "C3") (pin "1") (pinfunction "1_1") (pintype "passive"))
      (node (ref "C4") (pin "2") (pinfunction "2_2") (pintype "passive"))
      (node (ref "R16") (pin "1") (pinfunction "1_1") (pintype "passive"))
      (node (ref "U1") (pin "54") (pinfunction "VCCPLL0_54") (pintype "power_in"))
    )
    (net (code "101") (name "Net-(U1F-VCCPLL1)") (class "Default")
      (node (ref "C5") (pin "2") (pinfunction "2_2") (pintype "passive"))
      (node (ref "C6") (pin "2") (pinfunction "2_2") (pintype "passive"))
      (node (ref "R17") (pin "1") (pinfunction "1_1") (pintype "passive"))
      (node (ref "U1") (pin "126") (pinfunction "VCCPLL1_126") (pintype "power_in"))
    )
    (net (code "102") (name "Net-(U2-HOLD)") (class "Default")
      (node (ref "R14") (pin "7") (pinfunction "7_7") (pintype "passive"))
      (node (ref "U2") (pin "7") (pinfunction "HOLD_7") (pintype "input"))
    )
    (net (code "103") (name "Net-(U2-WP)") (class "Default")
      (node (ref "R14") (pin "5") (pinfunction "5_5") (pintype "passive"))
      (node (ref "U2") (pin "3") (pinfunction "WP_3") (pintype "input"))
    )
    (net (code "104") (name "unconnected-(U1A-IOT_168-Pad110)") (class "Default")
      (node (ref "U1") (pin "110") (pinfunction "IOT_168_110") (pintype "bidirectional+no_connect"))
    )
    (net (code "105") (name "unconnected-(U1A-IOT_169-Pad112)") (class "Default")
      (node (ref "U1") (pin "112") (pinfunction "IOT_169_112") (pintype "bidirectional+no_connect"))
    )
    (net (code "106") (name "unconnected-(U1A-IOT_170-Pad113)") (class "Default")
      (node (ref "U1") (pin "113") (pinfunction "IOT_170_113") (pintype "bidirectional+no_connect"))
    )
    (net (code "107") (name "unconnected-(U1A-IOT_179-Pad120)") (class "Default")
      (node (ref "U1") (pin "120") (pinfunction "IOT_179_120") (pintype "bidirectional+no_connect"))
    )
    (net (code "108") (name "unconnected-(U1A-IOT_181-Pad121)") (class "Default")
      (node (ref "U1") (pin "121") (pinfunction "IOT_181_121") (pintype "bidirectional+no_connect"))
    )
    (net (code "109") (name "unconnected-(U1A-IOT_190-Pad122)") (class "Default")
      (node (ref "U1") (pin "122") (pinfunction "IOT_190_122") (pintype "bidirectional+no_connect"))
    )
    (net (code "110") (name "unconnected-(U1A-IOT_191-Pad124)") (class "Default")
      (node (ref "U1") (pin "124") (pinfunction "IOT_191_124") (pintype "bidirectional+no_connect"))
    )
    (net (code "111") (name "unconnected-(U1A-IOT_192-Pad125)") (class "Default")
      (node (ref "U1") (pin "125") (pinfunction "IOT_192_125") (pintype "bidirectional+no_connect"))
    )
    (net (code "112") (name "unconnected-(U1A-IOT_197_GBIN1-Pad128)") (class "Default")
      (node (ref "U1") (pin "128") (pinfunction "IOT_197_GBIN1_128") (pintype "bidirectional+no_connect"))
    )
    (net (code "113") (name "unconnected-(U1A-IOT_198_GBIN0-Pad129)") (class "Default")
      (node (ref "U1") (pin "129") (pinfunction "IOT_198_GBIN0_129") (pintype "bidirectional+no_connect"))
    )
    (net (code "114") (name "unconnected-(U1A-IOT_206-Pad130)") (class "Default")
      (node (ref "U1") (pin "130") (pinfunction "IOT_206_130") (pintype "bidirectional+no_connect"))
    )
    (net (code "115") (name "unconnected-(U1A-IOT_212-Pad134)") (class "Default")
      (node (ref "U1") (pin "134") (pinfunction "IOT_212_134") (pintype "bidirectional+no_connect"))
    )
    (net (code "116") (name "unconnected-(U1A-IOT_213-Pad135)") (class "Default")
      (node (ref "U1") (pin "135") (pinfunction "IOT_213_135") (pintype "bidirectional+no_connect"))
    )
    (net (code "117") (name "unconnected-(U1A-IOT_214-Pad136)") (class "Default")
      (node (ref "U1") (pin "136") (pinfunction "IOT_214_136") (pintype "bidirectional+no_connect"))
    )
    (net (code "118") (name "unconnected-(U1A-IOT_215-Pad137)") (class "Default")
      (node (ref "U1") (pin "137") (pinfunction "IOT_215_137") (pintype "bidirectional+no_connect"))
    )
    (net (code "119") (name "unconnected-(U1A-IOT_216-Pad138)") (class "Default")
      (node (ref "U1") (pin "138") (pinfunction "IOT_216_138") (pintype "bidirectional+no_connect"))
    )
    (net (code "120") (name "unconnected-(U1A-IOT_217-Pad139)") (class "Default")
      (node (ref "U1") (pin "139") (pinfunction "IOT_217_139") (pintype "bidirectional+no_connect"))
    )
    (net (code "121") (name "unconnected-(U1A-IOT_219-Pad141)") (class "Default")
      (node (ref "U1") (pin "141") (pinfunction "IOT_219_141") (pintype "bidirectional+no_connect"))
    )
    (net (code "122") (name "unconnected-(U1A-IOT_220-Pad142)") (class "Default")
      (node (ref "U1") (pin "142") (pinfunction "IOT_220_142") (pintype "bidirectional+no_connect"))
    )
    (net (code "123") (name "unconnected-(U1A-IOT_221-Pad143)") (class "Default")
      (node (ref "U1") (pin "143") (pinfunction "IOT_221_143") (pintype "bidirectional+no_connect"))
    )
    (net (code "124") (name "unconnected-(U1A-IOT_222-Pad144)") (class "Default")
      (node (ref "U1") (pin "144") (pinfunction "IOT_222_144") (pintype "bidirectional+no_connect"))
    )
    (net (code "125") (name "unconnected-(U1B-IOR_109-Pad73)") (class "Default")
      (node (ref "U1") (pin "73") (pinfunction "IOR_109_73") (pintype "bidirectional+no_connect"))
    )
    (net (code "126") (name "unconnected-(U1B-IOR_110-Pad74)") (class "Default")
      (node (ref "U1") (pin "74") (pinfunction "IOR_110_74") (pintype "bidirectional+no_connect"))
    )
    (net (code "127") (name "unconnected-(U1B-IOR_111-Pad75)") (class "Default")
      (node (ref "U1") (pin "75") (pinfunction "IOR_111_75") (pintype "bidirectional+no_connect"))
    )
    (net (code "128") (name "unconnected-(U1B-IOR_112-Pad76)") (class "Default")
      (node (ref "U1") (pin "76") (pinfunction "IOR_112_76") (pintype "bidirectional+no_connect"))
    )
    (net (code "129") (name "unconnected-(U1B-IOR_114-Pad78)") (class "Default")
      (node (ref "U1") (pin "78") (pinfunction "IOR_114_78") (pintype "bidirectional+no_connect"))
    )
    (net (code "130") (name "unconnected-(U1B-IOR_115-Pad79)") (class "Default")
      (node (ref "U1") (pin "79") (pinfunction "IOR_115_79") (pintype "bidirectional+no_connect"))
    )
    (net (code "131") (name "unconnected-(U1B-IOR_116-Pad80)") (class "Default")
      (node (ref "U1") (pin "80") (pinfunction "IOR_116_80") (pintype "bidirectional+no_connect"))
    )
    (net (code "132") (name "unconnected-(U1B-IOR_117-Pad81)") (class "Default")
      (node (ref "U1") (pin "81") (pinfunction "IOR_117_81") (pintype "bidirectional+no_connect"))
    )
    (net (code "133") (name "unconnected-(U1B-IOR_118-Pad82)") (class "Default")
      (node (ref "U1") (pin "82") (pinfunction "IOR_118_82") (pintype "bidirectional+no_connect"))
    )
    (net (code "134") (name "unconnected-(U1B-IOR_128-Pad85)") (class "Default")
      (node (ref "U1") (pin "85") (pinfunction "IOR_128_85") (pintype "bidirectional+no_connect"))
    )
    (net (code "135") (name "unconnected-(U1B-IOR_136-Pad87)") (class "Default")
      (node (ref "U1") (pin "87") (pinfunction "IOR_136_87") (pintype "bidirectional+no_connect"))
    )
    (net (code "136") (name "unconnected-(U1B-IOR_137-Pad88)") (class "Default")
      (node (ref "U1") (pin "88") (pinfunction "IOR_137_88") (pintype "bidirectional+no_connect"))
    )
    (net (code "137") (name "unconnected-(U1B-IOR_139-Pad91)") (class "Default")
      (node (ref "U1") (pin "91") (pinfunction "IOR_139_91") (pintype "bidirectional+no_connect"))
    )
    (net (code "138") (name "unconnected-(U1B-IOR_140_GBIN3-Pad93)") (class "Default")
      (node (ref "U1") (pin "93") (pinfunction "IOR_140_GBIN3_93") (pintype "bidirectional+no_connect"))
    )
    (net (code "139") (name "unconnected-(U1B-IOR_141_GBIN2-Pad94)") (class "Default")
      (node (ref "U1") (pin "94") (pinfunction "IOR_141_GBIN2_94") (pintype "bidirectional+no_connect"))
    )
    (net (code "140") (name "unconnected-(U1B-IOR_144-Pad95)") (class "Default")
      (node (ref "U1") (pin "95") (pinfunction "IOR_144_95") (pintype "bidirectional+no_connect"))
    )
    (net (code "141") (name "unconnected-(U1B-IOR_146-Pad96)") (class "Default")
      (node (ref "U1") (pin "96") (pinfunction "IOR_146_96") (pintype "bidirectional+no_connect"))
    )
    (net (code "142") (name "unconnected-(U1B-IOR_147-Pad97)") (class "Default")
      (node (ref "U1") (pin "97") (pinfunction "IOR_147_97") (pintype "bidirectional+no_connect"))
    )
    (net (code "143") (name "unconnected-(U1B-IOR_148-Pad98)") (class "Default")
      (node (ref "U1") (pin "98") (pinfunction "IOR_148_98") (pintype "bidirectional+no_connect"))
    )
    (net (code "144") (name "unconnected-(U1B-IOR_152-Pad99)") (class "Default")
      (node (ref "U1") (pin "99") (pinfunction "IOR_152_99") (pintype "bidirectional+no_connect"))
    )
    (net (code "145") (name "unconnected-(U1B-IOR_160-Pad101)") (class "Default")
      (node (ref "U1") (pin "101") (pinfunction "IOR_160_101") (pintype "bidirectional+no_connect"))
    )
    (net (code "146") (name "unconnected-(U1B-IOR_161-Pad102)") (class "Default")
      (node (ref "U1") (pin "102") (pinfunction "IOR_161_102") (pintype "bidirectional+no_connect"))
    )
    (net (code "147") (name "unconnected-(U1B-IOR_164-Pad104)") (class "Default")
      (node (ref "U1") (pin "104") (pinfunction "IOR_164_104") (pintype "bidirectional+no_connect"))
    )
    (net (code "148") (name "unconnected-(U1B-IOR_165-Pad105)") (class "Default")
      (node (ref "U1") (pin "105") (pinfunction "IOR_165_105") (pintype "bidirectional+no_connect"))
    )
    (net (code "149") (name "unconnected-(U1B-IOR_166-Pad106)") (class "Default")
      (node (ref "U1") (pin "106") (pinfunction "IOR_166_106") (pintype "bidirectional+no_connect"))
    )
    (net (code "150") (name "unconnected-(U1B-IOR_167-Pad107)") (class "Default")
      (node (ref "U1") (pin "107") (pinfunction "IOR_167_107") (pintype "bidirectional+no_connect"))
    )
    (net (code "151") (name "unconnected-(U1C-IOB_91-Pad55)") (class "Default")
      (node (ref "U1") (pin "55") (pinfunction "IOB_91_55") (pintype "bidirectional+no_connect"))
    )
    (net (code "152") (name "unconnected-(U1D-IOL_8A-Pad11)") (class "Default")
      (node (ref "U1") (pin "11") (pinfunction "IOL_8A_11") (pintype "bidirectional+no_connect"))
    )
    (net (code "153") (name "unconnected-(U1D-IOL_8B-Pad12)") (class "Default")
      (node (ref "U1") (pin "12") (pinfunction "IOL_8B_12") (pintype "bidirectional+no_connect"))
    )
    (net (code "154") (name "unconnected-(U1D-IOL_10A-Pad15)") (class "Default")
      (node (ref "U1") (pin "15") (pinfunction "IOL_10A_15") (pintype "bidirectional+no_connect"))
    )
    (net (code "155") (name "unconnected-(U1D-IOL_10B-Pad16)") (class "Default")
      (node (ref "U1") (pin "16") (pinfunction "IOL_10B_16") (pintype "bidirectional+no_connect"))
    )
    (net (code "156") (name "unconnected-(U1D-IOL_12A-Pad17)") (class "Default")
      (node (ref "U1") (pin "17") (pinfunction "IOL_12A_17") (pintype "bidirectional+no_connect"))
    )
    (net (code "157") (name "unconnected-(U1D-IOL_12B-Pad18)") (class "Default")
      (node (ref "U1") (pin "18") (pinfunction "IOL_12B_18") (pintype "bidirectional+no_connect"))
    )
    (net (code "158") (name "unconnected-(U1D-IOL_17A-Pad23)") (class "Default")
      (node (ref "U1") (pin "23") (pinfunction "IOL_17A_23") (pintype "bidirectional+no_connect"))
    )
    (net (code "159") (name "unconnected-(U1D-IOL_17B-Pad24)") (class "Default")
      (node (ref "U1") (pin "24") (pinfunction "IOL_17B_24") (pintype "bidirectional+no_connect"))
    )
    (net (code "160") (name "unconnected-(U1D-IOL_18A-Pad25)") (class "Default")
      (node (ref "U1") (pin "25") (pinfunction "IOL_18A_25") (pintype "bidirectional+no_connect"))
    )
    (net (code "161") (name "unconnected-(U1D-IOL_18B-Pad26)") (class "Default")
      (node (ref "U1") (pin "26") (pinfunction "IOL_18B_26") (pintype "bidirectional+no_connect"))
    )
    (net (code "162") (name "unconnected-(U1D-IOL_23A-Pad28)") (class "Default")
      (node (ref "U1") (pin "28") (pinfunction "IOL_23A_28") (pintype "bidirectional+no_connect"))
    )
    (net (code "163") (name "unconnected-(U1D-IOL_23B-Pad29)") (class "Default")
      (node (ref "U1") (pin "29") (pinfunction "IOL_23B_29") (pintype "bidirectional+no_connect"))
    )
    (net (code "164") (name "unconnected-(U1D-IOL_24A-Pad31)") (class "Default")
      (node (ref "U1") (pin "31") (pinfunction "IOL_24A_31") (pintype "bidirectional+no_connect"))
    )
    (net (code "165") (name "unconnected-(U1D-IOL_24B-Pad32)") (class "Default")
      (node (ref "U1") (pin "32") (pinfunction "IOL_24B_32") (pintype "bidirectional+no_connect"))
    )
    (net (code "166") (name "unconnected-(U1F-NC-Pad35)") (class "Default")
      (node (ref "U1") (pin "35") (pinfunction "NC_35") (pintype "passive+no_connect"))
    )
    (net (code "167") (name "unconnected-(U1F-NC-Pad36)") (class "Default")
      (node (ref "U1") (pin "36") (pinfunction "NC_36") (pintype "passive+no_connect"))
    )
    (net (code "168") (name "unconnected-(U1F-NC-Pad50)") (class "Default")
      (node (ref "U1") (pin "50") (pinfunction "NC_50") (pintype "passive+no_connect"))
    )
    (net (code "169") (name "unconnected-(U1F-NC-Pad51)") (class "Default")
      (node (ref "U1") (pin "51") (pinfunction "NC_51") (pintype "passive+no_connect"))
    )
    (net (code "170") (name "unconnected-(U1F-NC-Pad58)") (class "Default")
      (node (ref "U1") (pin "58") (pinfunction "NC_58") (pintype "passive+no_connect"))
    )
    (net (code "171") (name "unconnected-(U1F-NC-Pad77)") (class "Default")
      (node (ref "U1") (pin "77") (pinfunction "NC_77") (pintype "passive+no_connect"))
    )
    (net (code "172") (name "unconnected-(U1F-NC-Pad133)") (class "Default")
      (node (ref "U1") (pin "133") (pinfunction "NC_133") (pintype "passive+no_connect"))
    )
    (net (code "173") (name "unconnected-(U1F-VPP_FAST-Pad109)") (class "Default")
      (node (ref "U1") (pin "109") (pinfunction "VPP_FAST_109") (pintype "power_in+no_connect"))
    )
  )
)
